# cpu.net
KiCad netlist of a schematic drawn in Altium Designer
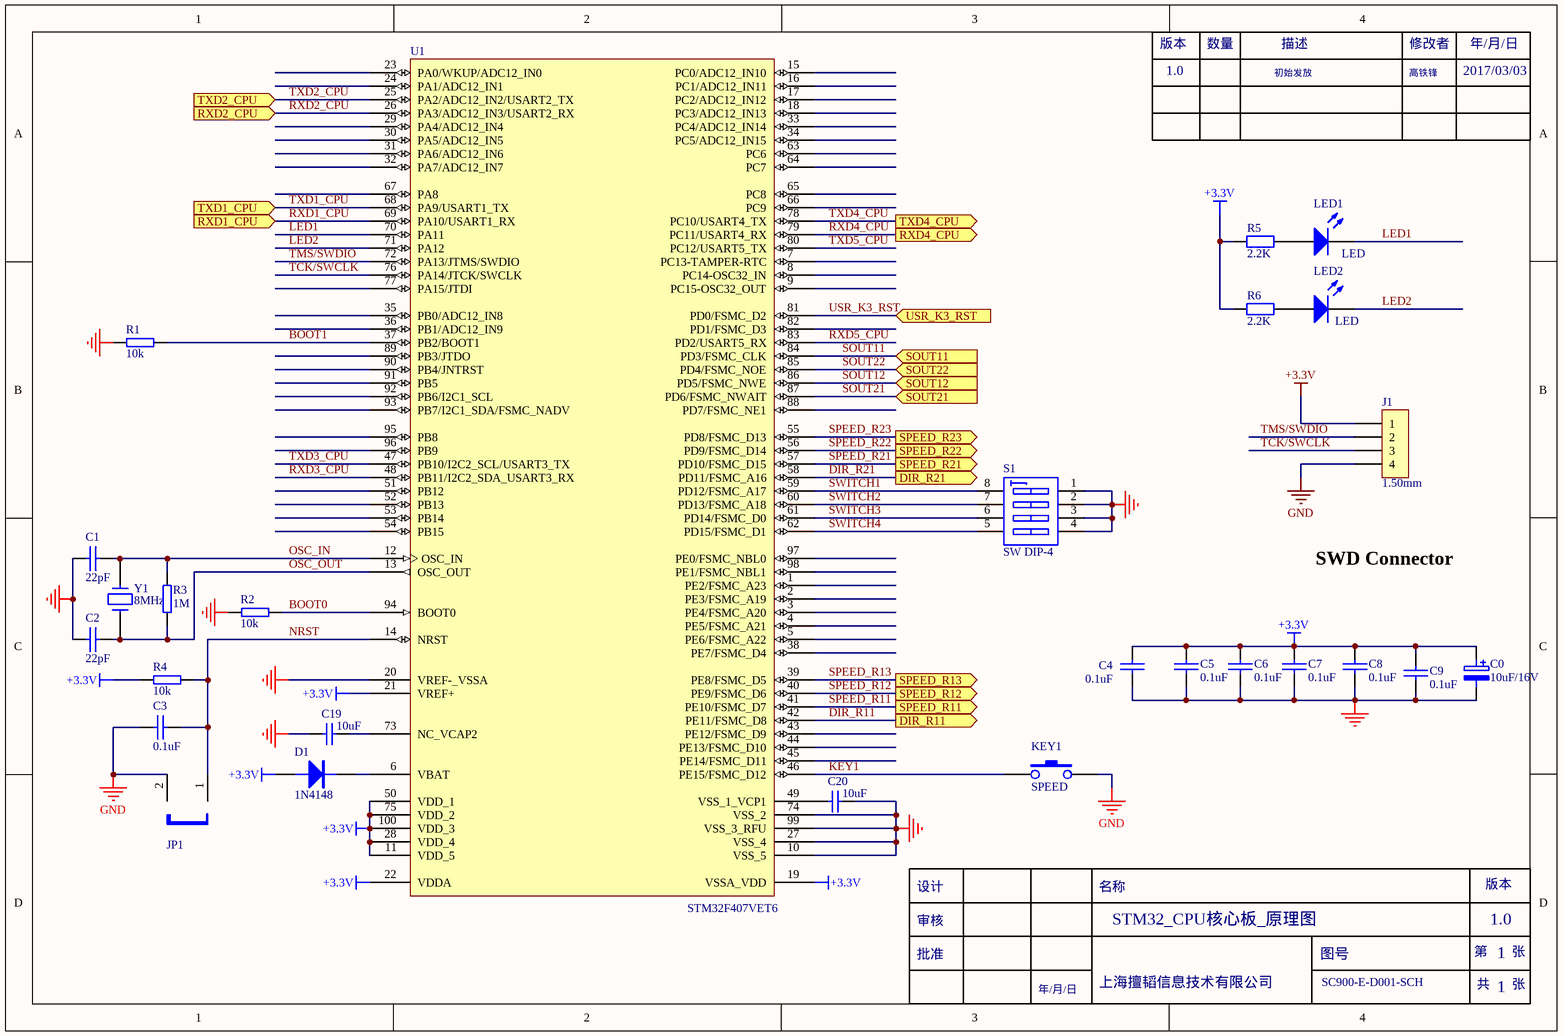
[diagram p0: cpu.SchDoc]

(export (version "E")
  (design (tool "Eeschema 10.0.6"))
  (components
    (comp (ref "C0")
      (value "10uF/16V")
      (footprint "CASE-A_3216")
      (description "Electrolytic Capacitor")
      (libsource (lib "Mylib") (part "ELECTRO2"))
    )
    (comp (ref "C1")
      (value "22pF")
      (footprint "0805_CAP")
      (description "Capacitor")
      (libsource (lib "Mylib") (part "CAP"))
    )
    (comp (ref "C2")
      (value "22pF")
      (footprint "0805_CAP")
      (description "Capacitor")
      (libsource (lib "Mylib") (part "CAP"))
    )
    (comp (ref "C3")
      (value "0.1uF")
      (footprint "0805_CAP")
      (description "Capacitor")
      (libsource (lib "Mylib") (part "CAP"))
    )
    (comp (ref "C4")
      (value "0.1uF")
      (footprint "0805_CAP")
      (description "Capacitor")
      (libsource (lib "Mylib") (part "CAP"))
    )
    (comp (ref "C5")
      (value "0.1uF")
      (footprint "0805_CAP")
      (description "Capacitor")
      (libsource (lib "Mylib") (part "CAP"))
    )
    (comp (ref "C6")
      (value "0.1uF")
      (footprint "0805_CAP")
      (description "Capacitor")
      (libsource (lib "Mylib") (part "CAP"))
    )
    (comp (ref "C7")
      (value "0.1uF")
      (footprint "0805_CAP")
      (description "Capacitor")
      (libsource (lib "Mylib") (part "CAP"))
    )
    (comp (ref "C8")
      (value "0.1uF")
      (footprint "0805_CAP")
      (description "Capacitor")
      (libsource (lib "Mylib") (part "CAP"))
    )
    (comp (ref "C9")
      (value "0.1uF")
      (footprint "0805_CAP")
      (description "Capacitor")
      (libsource (lib "Mylib") (part "CAP"))
    )
    (comp (ref "C19")
      (value "10uF")
      (footprint "0805_CAP")
      (description "贴片电容")
      (libsource (lib "Miscellaneous Devices LC") (part "0805 100nF(104) 10% 50V"))
    )
    (comp (ref "C20")
      (value "10uF")
      (footprint "0805_CAP")
      (description "贴片电容")
      (libsource (lib "Miscellaneous Devices LC") (part "0805 100nF(104) 10% 50V"))
    )
    (comp (ref "D1")
      (value "1N4148")
      (footprint "LL-34(玻璃二极管)")
      (description "LL-34(玻璃二极管)")
      (libsource (lib "MyLibrary") (part "DIODE"))
    )
    (comp (ref "J1")
      (value "1.50mm")
      (footprint "PH1.5_4P")
      (description "Connector")
      (libsource (lib "MyLibrary") (part "CON4"))
    )
    (comp (ref "JP1")
      (value "JUMPER")
      (footprint "SIP2")
      (description "2.54间距，2P，单排插针")
      (libsource (lib "MyLibrary") (part "JUMPER"))
    )
    (comp (ref "KEY1")
      (value "SPEED")
      (footprint "SW_PB_SMD_6X6")
      (libsource (lib "myIntegrated_Library1") (part "SW-KEY-2"))
    )
    (comp (ref "LED1")
      (value "LED")
      (footprint "0805-LED-R")
      (description "Typical RED, GREEN, YELLOW, AMBER GaAs LED")
      (fields (field (name "PUBLISHER") "Altium Limited"))
      (libsource (lib "Miscellaneous Devices") (part "LED2"))
    )
    (comp (ref "LED2")
      (value "LED")
      (footprint "0805-LED-R")
      (description "Typical RED, GREEN, YELLOW, AMBER GaAs LED")
      (fields (field (name "PUBLISHER") "Altium Limited"))
      (libsource (lib "Miscellaneous Devices") (part "LED2"))
    )
    (comp (ref "R1") (value "10k") (footprint "0805_RES") (libsource (lib "Mylib") (part "RES")))
    (comp (ref "R2") (value "10k") (footprint "0805_RES") (libsource (lib "Mylib") (part "RES")))
    (comp (ref "R3") (value "1M") (footprint "0805_RES") (libsource (lib "Mylib") (part "RES")))
    (comp (ref "R4") (value "10k") (footprint "0805_RES") (libsource (lib "Mylib") (part "RES")))
    (comp (ref "R5")
      (value "2.2K")
      (footprint "0805_RES")
      (description "Resistor")
      (fields (field (name "PUBLISHER") "Altium Limited"))
      (libsource (lib "Miscellaneous Devices") (part "Res2"))
    )
    (comp (ref "R6")
      (value "2.2K")
      (footprint "0805_RES")
      (description "Resistor")
      (fields (field (name "PUBLISHER") "Altium Limited"))
      (libsource (lib "Miscellaneous Devices") (part "Res2"))
    )
    (comp (ref "S1")
      (value "SW DIP-4")
      (footprint "SOP8_switch")
      (description "DIP Switch")
      (libsource (lib "MyLibrary") (part "SW DIP-4"))
    )
    (comp (ref "U1")
      (value "STM32F407VET6")
      (footprint "LQFP100_14x14")
      (description "STM32 ARM-based 32-bit MCU with 64 Kbytes Flash, 100-pin LQFP, Industrial Temperature")
      (libsource (lib "Mylib") (part "STM32F2xx_100"))
    )
    (comp (ref "Y1")
      (value "8MHz")
      (footprint "XTAL_US1")
      (description "Crystal")
      (libsource (lib "Mylib") (part "CRYSTAL"))
    )
  )
  (nets
    (net (code "1") (name "+3.3V") (class "Default")
      (node (ref "C0") (pin "1") (pinfunction "1_1") (pintype "passive"))
      (node (ref "C4") (pin "1") (pinfunction "1_1") (pintype "passive"))
      (node (ref "C5") (pin "1") (pinfunction "1_1") (pintype "passive"))
      (node (ref "C6") (pin "1") (pinfunction "1_1") (pintype "passive"))
      (node (ref "C7") (pin "1") (pinfunction "1_1") (pintype "passive"))
      (node (ref "C8") (pin "1") (pinfunction "1_1") (pintype "passive"))
      (node (ref "C9") (pin "1") (pinfunction "1_1") (pintype "passive"))
      (node (ref "D1") (pin "1") (pinfunction "A_1") (pintype "passive"))
      (node (ref "J1") (pin "1") (pinfunction "1_1") (pintype "passive"))
      (node (ref "R4") (pin "1") (pinfunction "1_1") (pintype "passive"))
      (node (ref "R5") (pin "2") (pinfunction "2_2") (pintype "passive"))
      (node (ref "R6") (pin "2") (pinfunction "2_2") (pintype "passive"))
      (node (ref "U1") (pin "100") (pinfunction "VDD_3_100") (pintype "power_in"))
      (node (ref "U1") (pin "11") (pinfunction "VDD_5_11") (pintype "power_in"))
      (node (ref "U1") (pin "19") (pinfunction "VSSA_VDD_19") (pintype "power_in"))
      (node (ref "U1") (pin "21") (pinfunction "VREF+_21") (pintype "power_in"))
      (node (ref "U1") (pin "22") (pinfunction "VDDA_22") (pintype "power_in"))
      (node (ref "U1") (pin "28") (pinfunction "VDD_4_28") (pintype "power_in"))
      (node (ref "U1") (pin "50") (pinfunction "VDD_1_50") (pintype "power_in"))
      (node (ref "U1") (pin "75") (pinfunction "VDD_2_75") (pintype "power_in"))
    )
    (net (code "2") (name "/BOOT0") (class "Default")
      (node (ref "R2") (pin "2") (pinfunction "2_2") (pintype "passive"))
      (node (ref "U1") (pin "94") (pinfunction "BOOT0_94") (pintype "input"))
    )
    (net (code "3") (name "/BOOT1") (class "Default")
      (node (ref "R1") (pin "2") (pinfunction "2_2") (pintype "passive"))
      (node (ref "U1") (pin "37") (pinfunction "PB2/BOOT1_37") (pintype "bidirectional"))
    )
    (net (code "4") (name "/DIR_R11") (class "Default")
      (node (ref "U1") (pin "42") (pinfunction "PE11/FSMC_D8_42") (pintype "bidirectional"))
    )
    (net (code "5") (name "/DIR_R21") (class "Default")
      (node (ref "U1") (pin "58") (pinfunction "PD11/FSMC_A16_58") (pintype "bidirectional"))
    )
    (net (code "6") (name "/KEY1") (class "Default")
      (node (ref "KEY1") (pin "1") (pinfunction "1_1") (pintype "passive"))
      (node (ref "U1") (pin "46") (pinfunction "PE15/FSMC_D12_46") (pintype "bidirectional"))
    )
    (net (code "7") (name "/LED1") (class "Default")
      (node (ref "LED1") (pin "2") (pinfunction "K_2") (pintype "passive"))
      (node (ref "U1") (pin "70") (pinfunction "PA11_70") (pintype "bidirectional"))
    )
    (net (code "8") (name "/LED2") (class "Default")
      (node (ref "LED2") (pin "2") (pinfunction "K_2") (pintype "passive"))
      (node (ref "U1") (pin "71") (pinfunction "PA12_71") (pintype "bidirectional"))
    )
    (net (code "9") (name "/NRST") (class "Default")
      (node (ref "C3") (pin "2") (pinfunction "2_2") (pintype "passive"))
      (node (ref "JP1") (pin "1") (pinfunction "1_1") (pintype "passive"))
      (node (ref "R4") (pin "2") (pinfunction "2_2") (pintype "passive"))
      (node (ref "U1") (pin "14") (pinfunction "NRST_14") (pintype "bidirectional"))
    )
    (net (code "10") (name "/OSC_IN") (class "Default")
      (node (ref "C1") (pin "2") (pinfunction "2_2") (pintype "passive"))
      (node (ref "R3") (pin "2") (pinfunction "2_2") (pintype "passive"))
      (node (ref "U1") (pin "12") (pinfunction "OSC_IN_12") (pintype "input"))
      (node (ref "Y1") (pin "2") (pinfunction "2_2") (pintype "passive"))
    )
    (net (code "11") (name "/OSC_OUT") (class "Default")
      (node (ref "C2") (pin "2") (pinfunction "2_2") (pintype "passive"))
      (node (ref "R3") (pin "1") (pinfunction "1_1") (pintype "passive"))
      (node (ref "U1") (pin "13") (pinfunction "OSC_OUT_13") (pintype "output"))
      (node (ref "Y1") (pin "1") (pinfunction "1_1") (pintype "passive"))
    )
    (net (code "12") (name "/RXD1_CPU") (class "Default")
      (node (ref "U1") (pin "69") (pinfunction "PA10/USART1_RX_69") (pintype "bidirectional"))
    )
    (net (code "13") (name "/RXD2_CPU") (class "Default")
      (node (ref "U1") (pin "26") (pinfunction "PA3/ADC12_IN3/USART2_RX_26") (pintype "bidirectional"))
    )
    (net (code "14") (name "/RXD3_CPU") (class "Default")
      (node (ref "U1") (pin "48") (pinfunction "PB11/I2C2_SDA_USART3_RX_48") (pintype "bidirectional"))
    )
    (net (code "15") (name "/RXD4_CPU") (class "Default")
      (node (ref "U1") (pin "79") (pinfunction "PC11/USART4_RX_79") (pintype "bidirectional"))
    )
    (net (code "16") (name "/RXD5_CPU") (class "Default")
      (node (ref "U1") (pin "83") (pinfunction "PD2/USART5_RX_83") (pintype "bidirectional"))
    )
    (net (code "17") (name "/SOUT11") (class "Default")
      (node (ref "U1") (pin "84") (pinfunction "PD3/FSMC_CLK_84") (pintype "bidirectional"))
    )
    (net (code "18") (name "/SOUT12") (class "Default")
      (node (ref "U1") (pin "86") (pinfunction "PD5/FSMC_NWE_86") (pintype "bidirectional"))
    )
    (net (code "19") (name "/SOUT21") (class "Default")
      (node (ref "U1") (pin "87") (pinfunction "PD6/FSMC_NWAIT_87") (pintype "bidirectional"))
    )
    (net (code "20") (name "/SOUT22") (class "Default")
      (node (ref "U1") (pin "85") (pinfunction "PD4/FSMC_NOE_85") (pintype "bidirectional"))
    )
    (net (code "21") (name "/SPEED_R11") (class "Default")
      (node (ref "U1") (pin "41") (pinfunction "PE10/FSMC_D7_41") (pintype "bidirectional"))
    )
    (net (code "22") (name "/SPEED_R12") (class "Default")
      (node (ref "U1") (pin "40") (pinfunction "PE9/FSMC_D6_40") (pintype "bidirectional"))
    )
    (net (code "23") (name "/SPEED_R13") (class "Default")
      (node (ref "U1") (pin "39") (pinfunction "PE8/FSMC_D5_39") (pintype "bidirectional"))
    )
    (net (code "24") (name "/SPEED_R21") (class "Default")
      (node (ref "U1") (pin "57") (pinfunction "PD10/FSMC_D15_57") (pintype "bidirectional"))
    )
    (net (code "25") (name "/SPEED_R22") (class "Default")
      (node (ref "U1") (pin "56") (pinfunction "PD9/FSMC_D14_56") (pintype "bidirectional"))
    )
    (net (code "26") (name "/SPEED_R23") (class "Default")
      (node (ref "U1") (pin "55") (pinfunction "PD8/FSMC_D13_55") (pintype "bidirectional"))
    )
    (net (code "27") (name "/SWITCH1") (class "Default")
      (node (ref "S1") (pin "8") (pinfunction "B5_8") (pintype "passive"))
      (node (ref "U1") (pin "59") (pinfunction "PD12/FSMC_A17_59") (pintype "bidirectional"))
    )
    (net (code "28") (name "/SWITCH2") (class "Default")
      (node (ref "S1") (pin "7") (pinfunction "B6_7") (pintype "passive"))
      (node (ref "U1") (pin "60") (pinfunction "PD13/FSMC_A18_60") (pintype "bidirectional"))
    )
    (net (code "29") (name "/SWITCH3") (class "Default")
      (node (ref "S1") (pin "6") (pinfunction "A6_6") (pintype "passive"))
      (node (ref "U1") (pin "61") (pinfunction "PD14/FSMC_D0_61") (pintype "bidirectional"))
    )
    (net (code "30") (name "/SWITCH4") (class "Default")
      (node (ref "S1") (pin "5") (pinfunction "A5_5") (pintype "passive"))
      (node (ref "U1") (pin "62") (pinfunction "PD15/FSMC_D1_62") (pintype "bidirectional"))
    )
    (net (code "31") (name "/TCK{slash}SWCLK") (class "Default")
      (node (ref "J1") (pin "3") (pinfunction "3_3") (pintype "passive"))
      (node (ref "U1") (pin "76") (pinfunction "PA14/JTCK/SWCLK_76") (pintype "bidirectional"))
    )
    (net (code "32") (name "/TMS{slash}SWDIO") (class "Default")
      (node (ref "J1") (pin "2") (pinfunction "2_2") (pintype "passive"))
      (node (ref "U1") (pin "72") (pinfunction "PA13/JTMS/SWDIO_72") (pintype "bidirectional"))
    )
    (net (code "33") (name "/TXD1_CPU") (class "Default")
      (node (ref "U1") (pin "68") (pinfunction "PA9/USART1_TX_68") (pintype "bidirectional"))
    )
    (net (code "34") (name "/TXD2_CPU") (class "Default")
      (node (ref "U1") (pin "25") (pinfunction "PA2/ADC12_IN2/USART2_TX_25") (pintype "bidirectional"))
    )
    (net (code "35") (name "/TXD3_CPU") (class "Default")
      (node (ref "U1") (pin "47") (pinfunction "PB10/I2C2_SCL/USART3_TX_47") (pintype "bidirectional"))
    )
    (net (code "36") (name "/TXD4_CPU") (class "Default")
      (node (ref "U1") (pin "78") (pinfunction "PC10/USART4_TX_78") (pintype "bidirectional"))
    )
    (net (code "37") (name "/TXD5_CPU") (class "Default")
      (node (ref "U1") (pin "80") (pinfunction "PC12/USART5_TX_80") (pintype "bidirectional"))
    )
    (net (code "38") (name "/USR_K3_RST") (class "Default")
      (node (ref "U1") (pin "81") (pinfunction "PD0/FSMC_D2_81") (pintype "bidirectional"))
    )
    (net (code "39") (name "GND") (class "Default")
      (node (ref "C0") (pin "2") (pinfunction "2_2") (pintype "passive"))
      (node (ref "C1") (pin "1") (pinfunction "1_1") (pintype "passive"))
      (node (ref "C19") (pin "2") (pinfunction "2_2") (pintype "passive"))
      (node (ref "C2") (pin "1") (pinfunction "1_1") (pintype "passive"))
      (node (ref "C20") (pin "1") (pinfunction "1_1") (pintype "passive"))
      (node (ref "C3") (pin "1") (pinfunction "1_1") (pintype "passive"))
      (node (ref "C4") (pin "2") (pinfunction "2_2") (pintype "passive"))
      (node (ref "C5") (pin "2") (pinfunction "2_2") (pintype "passive"))
      (node (ref "C6") (pin "2") (pinfunction "2_2") (pintype "passive"))
      (node (ref "C7") (pin "2") (pinfunction "2_2") (pintype "passive"))
      (node (ref "C8") (pin "2") (pinfunction "2_2") (pintype "passive"))
      (node (ref "C9") (pin "2") (pinfunction "2_2") (pintype "passive"))
      (node (ref "J1") (pin "4") (pinfunction "4_4") (pintype "passive"))
      (node (ref "JP1") (pin "2") (pinfunction "2_2") (pintype "passive"))
      (node (ref "KEY1") (pin "2") (pinfunction "2_2") (pintype "passive"))
      (node (ref "R1") (pin "1") (pinfunction "1_1") (pintype "passive"))
      (node (ref "R2") (pin "1") (pinfunction "1_1") (pintype "passive"))
      (node (ref "S1") (pin "1") (pinfunction "A1_1") (pintype "passive"))
      (node (ref "S1") (pin "2") (pinfunction "A2_2") (pintype "passive"))
      (node (ref "S1") (pin "3") (pinfunction "A3_3") (pintype "passive"))
      (node (ref "S1") (pin "4") (pinfunction "A4_4") (pintype "passive"))
      (node (ref "U1") (pin "10") (pinfunction "VSS_5_10") (pintype "power_in"))
      (node (ref "U1") (pin "20") (pinfunction "VREF-_VSSA_20") (pintype "power_in"))
      (node (ref "U1") (pin "27") (pinfunction "VSS_4_27") (pintype "power_in"))
      (node (ref "U1") (pin "74") (pinfunction "VSS_2_74") (pintype "power_in"))
      (node (ref "U1") (pin "99") (pinfunction "VSS_3_RFU_99") (pintype "power_in"))
    )
    (net (code "40") (name "Net-(D1-K)") (class "Default")
      (node (ref "D1") (pin "2") (pinfunction "K_2") (pintype "passive"))
      (node (ref "U1") (pin "6") (pinfunction "VBAT_6") (pintype "power_in"))
    )
    (net (code "41") (name "Net-(LED1-A)") (class "Default")
      (node (ref "LED1") (pin "1") (pinfunction "A_1") (pintype "passive"))
      (node (ref "R5") (pin "1") (pinfunction "1_1") (pintype "passive"))
    )
    (net (code "42") (name "Net-(LED2-A)") (class "Default")
      (node (ref "LED2") (pin "1") (pinfunction "A_1") (pintype "passive"))
      (node (ref "R6") (pin "1") (pinfunction "1_1") (pintype "passive"))
    )
    (net (code "43") (name "Net-(U1-NC_VCAP2)") (class "Default")
      (node (ref "C19") (pin "1") (pinfunction "1_1") (pintype "passive"))
      (node (ref "U1") (pin "73") (pinfunction "NC_VCAP2_73") (pintype "passive"))
    )
    (net (code "44") (name "Net-(U1-VSS_1_VCP1)") (class "Default")
      (node (ref "C20") (pin "2") (pinfunction "2_2") (pintype "passive"))
      (node (ref "U1") (pin "49") (pinfunction "VSS_1_VCP1_49") (pintype "power_in"))
    )
    (net (code "45") (name "unconnected-(U1-PA0{slash}WKUP{slash}ADC12_IN0-Pad23)") (class "Default")
      (node (ref "U1") (pin "23") (pinfunction "PA0/WKUP/ADC12_IN0_23") (pintype "bidirectional"))
    )
    (net (code "46") (name "unconnected-(U1-PA1{slash}ADC12_IN1-Pad24)") (class "Default")
      (node (ref "U1") (pin "24") (pinfunction "PA1/ADC12_IN1_24") (pintype "bidirectional"))
    )
    (net (code "47") (name "unconnected-(U1-PA4{slash}ADC12_IN4-Pad29)") (class "Default")
      (node (ref "U1") (pin "29") (pinfunction "PA4/ADC12_IN4_29") (pintype "bidirectional"))
    )
    (net (code "48") (name "unconnected-(U1-PA5{slash}ADC12_IN5-Pad30)") (class "Default")
      (node (ref "U1") (pin "30") (pinfunction "PA5/ADC12_IN5_30") (pintype "bidirectional"))
    )
    (net (code "49") (name "unconnected-(U1-PA6{slash}ADC12_IN6-Pad31)") (class "Default")
      (node (ref "U1") (pin "31") (pinfunction "PA6/ADC12_IN6_31") (pintype "bidirectional"))
    )
    (net (code "50") (name "unconnected-(U1-PA7{slash}ADC12_IN7-Pad32)") (class "Default")
      (node (ref "U1") (pin "32") (pinfunction "PA7/ADC12_IN7_32") (pintype "bidirectional"))
    )
    (net (code "51") (name "unconnected-(U1-PA8-Pad67)") (class "Default")
      (node (ref "U1") (pin "67") (pinfunction "PA8_67") (pintype "bidirectional"))
    )
    (net (code "52") (name "unconnected-(U1-PA15{slash}JTDI-Pad77)") (class "Default")
      (node (ref "U1") (pin "77") (pinfunction "PA15/JTDI_77") (pintype "bidirectional"))
    )
    (net (code "53") (name "unconnected-(U1-PB0{slash}ADC12_IN8-Pad35)") (class "Default")
      (node (ref "U1") (pin "35") (pinfunction "PB0/ADC12_IN8_35") (pintype "bidirectional"))
    )
    (net (code "54") (name "unconnected-(U1-PB1{slash}ADC12_IN9-Pad36)") (class "Default")
      (node (ref "U1") (pin "36") (pinfunction "PB1/ADC12_IN9_36") (pintype "bidirectional"))
    )
    (net (code "55") (name "unconnected-(U1-PB3{slash}JTDO-Pad89)") (class "Default")
      (node (ref "U1") (pin "89") (pinfunction "PB3/JTDO_89") (pintype "bidirectional"))
    )
    (net (code "56") (name "unconnected-(U1-PB4{slash}JNTRST-Pad90)") (class "Default")
      (node (ref "U1") (pin "90") (pinfunction "PB4/JNTRST_90") (pintype "bidirectional"))
    )
    (net (code "57") (name "unconnected-(U1-PB5-Pad91)") (class "Default")
      (node (ref "U1") (pin "91") (pinfunction "PB5_91") (pintype "bidirectional"))
    )
    (net (code "58") (name "unconnected-(U1-PB6{slash}I2C1_SCL-Pad92)") (class "Default")
      (node (ref "U1") (pin "92") (pinfunction "PB6/I2C1_SCL_92") (pintype "bidirectional"))
    )
    (net (code "59") (name "unconnected-(U1-PB7{slash}I2C1_SDA{slash}FSMC_NADV-Pad93)") (class "Default")
      (node (ref "U1") (pin "93") (pinfunction "PB7/I2C1_SDA/FSMC_NADV_93") (pintype "bidirectional"))
    )
    (net (code "60") (name "unconnected-(U1-PB8-Pad95)") (class "Default")
      (node (ref "U1") (pin "95") (pinfunction "PB8_95") (pintype "bidirectional"))
    )
    (net (code "61") (name "unconnected-(U1-PB9-Pad96)") (class "Default")
      (node (ref "U1") (pin "96") (pinfunction "PB9_96") (pintype "bidirectional"))
    )
    (net (code "62") (name "unconnected-(U1-PB12-Pad51)") (class "Default")
      (node (ref "U1") (pin "51") (pinfunction "PB12_51") (pintype "bidirectional"))
    )
    (net (code "63") (name "unconnected-(U1-PB13-Pad52)") (class "Default")
      (node (ref "U1") (pin "52") (pinfunction "PB13_52") (pintype "bidirectional"))
    )
    (net (code "64") (name "unconnected-(U1-PB14-Pad53)") (class "Default")
      (node (ref "U1") (pin "53") (pinfunction "PB14_53") (pintype "bidirectional"))
    )
    (net (code "65") (name "unconnected-(U1-PB15-Pad54)") (class "Default")
      (node (ref "U1") (pin "54") (pinfunction "PB15_54") (pintype "bidirectional"))
    )
    (net (code "66") (name "unconnected-(U1-PC0{slash}ADC12_IN10-Pad15)") (class "Default")
      (node (ref "U1") (pin "15") (pinfunction "PC0/ADC12_IN10_15") (pintype "bidirectional"))
    )
    (net (code "67") (name "unconnected-(U1-PC1{slash}ADC12_IN11-Pad16)") (class "Default")
      (node (ref "U1") (pin "16") (pinfunction "PC1/ADC12_IN11_16") (pintype "bidirectional"))
    )
    (net (code "68") (name "unconnected-(U1-PC2{slash}ADC12_IN12-Pad17)") (class "Default")
      (node (ref "U1") (pin "17") (pinfunction "PC2/ADC12_IN12_17") (pintype "bidirectional"))
    )
    (net (code "69") (name "unconnected-(U1-PC3{slash}ADC12_IN13-Pad18)") (class "Default")
      (node (ref "U1") (pin "18") (pinfunction "PC3/ADC12_IN13_18") (pintype "bidirectional"))
    )
    (net (code "70") (name "unconnected-(U1-PC4{slash}ADC12_IN14-Pad33)") (class "Default")
      (node (ref "U1") (pin "33") (pinfunction "PC4/ADC12_IN14_33") (pintype "bidirectional"))
    )
    (net (code "71") (name "unconnected-(U1-PC5{slash}ADC12_IN15-Pad34)") (class "Default")
      (node (ref "U1") (pin "34") (pinfunction "PC5/ADC12_IN15_34") (pintype "bidirectional"))
    )
    (net (code "72") (name "unconnected-(U1-PC6-Pad63)") (class "Default")
      (node (ref "U1") (pin "63") (pinfunction "PC6_63") (pintype "bidirectional"))
    )
    (net (code "73") (name "unconnected-(U1-PC7-Pad64)") (class "Default")
      (node (ref "U1") (pin "64") (pinfunction "PC7_64") (pintype "bidirectional"))
    )
    (net (code "74") (name "unconnected-(U1-PC8-Pad65)") (class "Default")
      (node (ref "U1") (pin "65") (pinfunction "PC8_65") (pintype "bidirectional"))
    )
    (net (code "75") (name "unconnected-(U1-PC9-Pad66)") (class "Default")
      (node (ref "U1") (pin "66") (pinfunction "PC9_66") (pintype "bidirectional"))
    )
    (net (code "76") (name "unconnected-(U1-PC13-TAMPER-RTC-Pad7)") (class "Default")
      (node (ref "U1") (pin "7") (pinfunction "PC13-TAMPER-RTC_7") (pintype "bidirectional"))
    )
    (net (code "77") (name "unconnected-(U1-PC14-OSC32_IN-Pad8)") (class "Default")
      (node (ref "U1") (pin "8") (pinfunction "PC14-OSC32_IN_8") (pintype "bidirectional"))
    )
    (net (code "78") (name "unconnected-(U1-PC15-OSC32_OUT-Pad9)") (class "Default")
      (node (ref "U1") (pin "9") (pinfunction "PC15-OSC32_OUT_9") (pintype "bidirectional"))
    )
    (net (code "79") (name "unconnected-(U1-PD1{slash}FSMC_D3-Pad82)") (class "Default")
      (node (ref "U1") (pin "82") (pinfunction "PD1/FSMC_D3_82") (pintype "bidirectional"))
    )
    (net (code "80") (name "unconnected-(U1-PD7{slash}FSMC_NE1-Pad88)") (class "Default")
      (node (ref "U1") (pin "88") (pinfunction "PD7/FSMC_NE1_88") (pintype "bidirectional"))
    )
    (net (code "81") (name "unconnected-(U1-PE0{slash}FSMC_NBL0-Pad97)") (class "Default")
      (node (ref "U1") (pin "97") (pinfunction "PE0/FSMC_NBL0_97") (pintype "bidirectional"))
    )
    (net (code "82") (name "unconnected-(U1-PE1{slash}FSMC_NBL1-Pad98)") (class "Default")
      (node (ref "U1") (pin "98") (pinfunction "PE1/FSMC_NBL1_98") (pintype "bidirectional"))
    )
    (net (code "83") (name "unconnected-(U1-PE2{slash}FSMC_A23-Pad1)") (class "Default")
      (node (ref "U1") (pin "1") (pinfunction "PE2/FSMC_A23_1") (pintype "bidirectional"))
    )
    (net (code "84") (name "unconnected-(U1-PE3{slash}FSMC_A19-Pad2)") (class "Default")
      (node (ref "U1") (pin "2") (pinfunction "PE3/FSMC_A19_2") (pintype "bidirectional"))
    )
    (net (code "85") (name "unconnected-(U1-PE4{slash}FSMC_A20-Pad3)") (class "Default")
      (node (ref "U1") (pin "3") (pinfunction "PE4/FSMC_A20_3") (pintype "bidirectional"))
    )
    (net (code "86") (name "unconnected-(U1-PE5{slash}FSMC_A21-Pad4)") (class "Default")
      (node (ref "U1") (pin "4") (pinfunction "PE5/FSMC_A21_4") (pintype "bidirectional"))
    )
    (net (code "87") (name "unconnected-(U1-PE6{slash}FSMC_A22-Pad5)") (class "Default")
      (node (ref "U1") (pin "5") (pinfunction "PE6/FSMC_A22_5") (pintype "bidirectional"))
    )
    (net (code "88") (name "unconnected-(U1-PE7{slash}FSMC_D4-Pad38)") (class "Default")
      (node (ref "U1") (pin "38") (pinfunction "PE7/FSMC_D4_38") (pintype "bidirectional"))
    )
    (net (code "89") (name "unconnected-(U1-PE12{slash}FSMC_D9-Pad43)") (class "Default")
      (node (ref "U1") (pin "43") (pinfunction "PE12/FSMC_D9_43") (pintype "bidirectional"))
    )
    (net (code "90") (name "unconnected-(U1-PE13{slash}FSMC_D10-Pad44)") (class "Default")
      (node (ref "U1") (pin "44") (pinfunction "PE13/FSMC_D10_44") (pintype "bidirectional"))
    )
    (net (code "91") (name "unconnected-(U1-PE14{slash}FSMC_D11-Pad45)") (class "Default")
      (node (ref "U1") (pin "45") (pinfunction "PE14/FSMC_D11_45") (pintype "bidirectional"))
    )
  )
)
